# PWR_SW_AND_VI_SENSE.net
KiCad netlist of a schematic drawn in Altium Designer
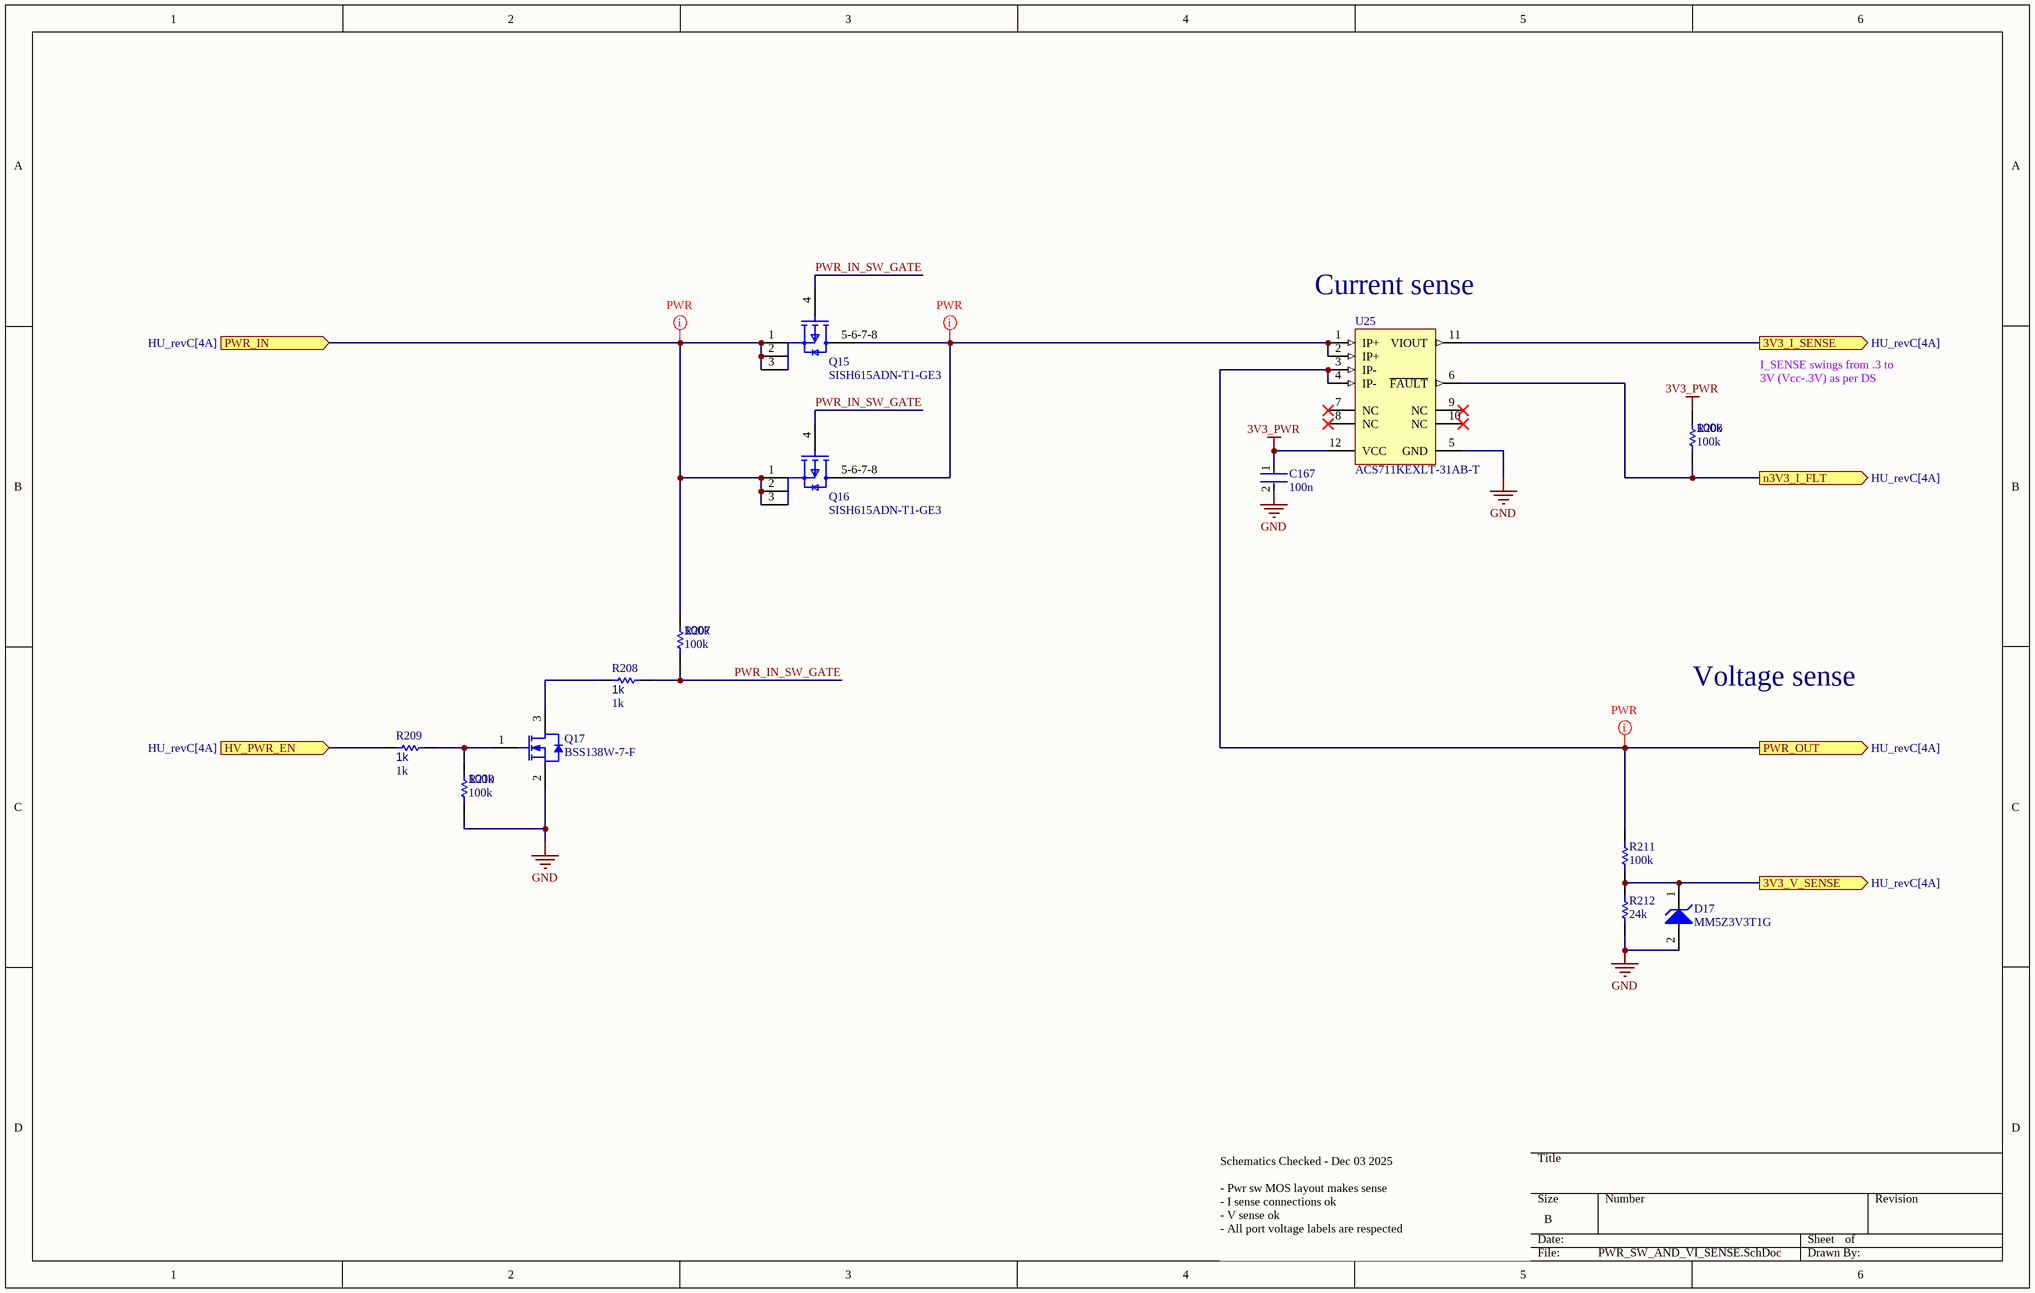
[diagram p0: PWR_SW_AND_VI_SENSE.SchDoc]

(export (version "E")
  (design (tool "Eeschema 10.0.6"))
  (components
    (comp (ref "C167")
      (value "100n")
      (footprint "FP-0402-L_1_0_0_05-W_0_5-IPC_A")
      (description "LARGE PADS, 0402 CAP, CHANGE COMMENT TO MATCH REAL P/N")
      (libsource (lib "Space Concordia") (part "b4654b650e69147ec39a6b967a45e02"))
    )
    (comp (ref "D17")
      (value "MM5Z3V3T1G")
      (footprint "ONSC-SOD-523-2-502-01_V")
      (description "Zener Voltage Regulator, 500 mW, 2-Pin SOD-523, Pb-Free, Tape and Reel")
      (fields (field (name "MANUFACTURER") "On Semiconductor"))
      (libsource (lib "Altium Content Vault") (part "ONSC-K1A2-2"))
    )
    (comp (ref "Q15")
      (value "SISH615ADN-T1-GE3")
      (footprint "SISH615ADN-T1-GE3-Footprint-1")
      (description "Trans MOSFET P-CH 20V 22.1A 8-Pin PowerPAK 1212 EP T/R")
      (libsource (lib "Space Concordia") (part "CMP-013-00036-4"))
    )
    (comp (ref "Q16")
      (value "SISH615ADN-T1-GE3")
      (footprint "SISH615ADN-T1-GE3-Footprint-1")
      (description "Trans MOSFET P-CH 20V 22.1A 8-Pin PowerPAK 1212 EP T/R")
      (libsource (lib "Space Concordia") (part "CMP-013-00036-4"))
    )
    (comp (ref "Q17")
      (value "BSS138W-7-F")
      (footprint "DIOD-SOT323-3_V")
      (fields (field (name "MANUFACTURER") "DiodesIncorporated"))
      (libsource (lib "Altium Content Vault") (part "NEMOS-GSD-3"))
    )
    (comp (ref "R206")
      (value "100k")
      (footprint "R0603B")
      (description "Resistor")
      (fields (field (name "ALTIUM_VALUE") "100k"))
      (libsource (lib "Space Concordia") (part "Resistor"))
    )
    (comp (ref "R207")
      (value "100k")
      (footprint "R0603B")
      (description "Resistor")
      (fields (field (name "ALTIUM_VALUE") "100k"))
      (libsource (lib "Space Concordia") (part "Resistor"))
    )
    (comp (ref "R208")
      (value "1k")
      (footprint "R0603B")
      (description "Resistor")
      (fields (field (name "ALTIUM_VALUE") "1k"))
      (libsource (lib "Space Concordia") (part "Resistor"))
    )
    (comp (ref "R209")
      (value "1k")
      (footprint "R0603B")
      (description "Resistor")
      (fields (field (name "ALTIUM_VALUE") "1k"))
      (libsource (lib "Space Concordia") (part "Resistor"))
    )
    (comp (ref "R210")
      (value "100k")
      (footprint "R0603B")
      (description "Resistor")
      (fields (field (name "ALTIUM_VALUE") "100k"))
      (libsource (lib "Space Concordia") (part "Resistor"))
    )
    (comp (ref "R211")
      (value "100k")
      (footprint "R0603B")
      (description "Resistor")
      (libsource (lib "Space Concordia") (part "Resistor"))
    )
    (comp (ref "R212")
      (value "24k")
      (footprint "R0603B")
      (description "Resistor")
      (libsource (lib "Space Concordia") (part "Resistor"))
    )
    (comp (ref "U25")
      (value "ACS711KEXLT-31AB-T")
      (footprint "ALEG-EX-12_V")
      (libsource (lib "Altium Content Vault") (part "ALEG-ACS711-QFN-12"))
    )
  )
  (nets
    (net (code "1") (name "/3V3_I_SENSE") (class "Default")
      (node (ref "U25") (pin "11") (pinfunction "VIOUT_11") (pintype "output"))
    )
    (net (code "2") (name "/3V3_V_SENSE") (class "Default")
      (node (ref "D17") (pin "1") (pinfunction "K_1") (pintype "passive"))
      (node (ref "R211") (pin "1") (pinfunction "1_1") (pintype "passive"))
      (node (ref "R212") (pin "2") (pinfunction "2_2") (pintype "passive"))
    )
    (net (code "3") (name "/HV_PWR_EN") (class "Default")
      (node (ref "R209") (pin "1") (pinfunction "1_1") (pintype "passive"))
    )
    (net (code "4") (name "/PWR_IN") (class "Default")
      (node (ref "Q15") (pin "1") (pinfunction "S_1") (pintype "passive"))
      (node (ref "Q15") (pin "2") (pinfunction "S_2") (pintype "passive"))
      (node (ref "Q15") (pin "3") (pinfunction "S_3") (pintype "passive"))
      (node (ref "Q16") (pin "1") (pinfunction "S_1") (pintype "passive"))
      (node (ref "Q16") (pin "2") (pinfunction "S_2") (pintype "passive"))
      (node (ref "Q16") (pin "3") (pinfunction "S_3") (pintype "passive"))
      (node (ref "R207") (pin "2") (pinfunction "2_2") (pintype "passive"))
    )
    (net (code "5") (name "/PWR_IN_SW_GATE") (class "Default")
      (node (ref "Q15") (pin "4") (pinfunction "G_4") (pintype "passive"))
      (node (ref "Q16") (pin "4") (pinfunction "G_4") (pintype "passive"))
      (node (ref "R207") (pin "1") (pinfunction "1_1") (pintype "passive"))
      (node (ref "R208") (pin "2") (pinfunction "2_2") (pintype "passive"))
    )
    (net (code "6") (name "/PWR_OUT") (class "Default")
      (node (ref "R211") (pin "2") (pinfunction "2_2") (pintype "passive"))
      (node (ref "U25") (pin "3") (pinfunction "IP-_3") (pintype "input"))
      (node (ref "U25") (pin "4") (pinfunction "IP-_4") (pintype "input"))
    )
    (net (code "7") (name "/n3V3_I_FLT") (class "Default")
      (node (ref "R206") (pin "1") (pinfunction "1_1") (pintype "passive"))
      (node (ref "U25") (pin "6") (pinfunction "~{FAULT}_6") (pintype "output"))
    )
    (net (code "8") (name "3V3_PWR") (class "Default")
      (node (ref "C167") (pin "1") (pinfunction "1_1") (pintype "passive"))
      (node (ref "R206") (pin "2") (pinfunction "2_2") (pintype "passive"))
      (node (ref "U25") (pin "12") (pinfunction "VCC_12") (pintype "power_in"))
    )
    (net (code "9") (name "GND") (class "Default")
      (node (ref "C167") (pin "2") (pinfunction "2_2") (pintype "passive"))
      (node (ref "D17") (pin "2") (pinfunction "A_2") (pintype "passive"))
      (node (ref "Q17") (pin "2") (pinfunction "S_2") (pintype "passive"))
      (node (ref "R210") (pin "1") (pinfunction "1_1") (pintype "passive"))
      (node (ref "R212") (pin "1") (pinfunction "1_1") (pintype "passive"))
      (node (ref "U25") (pin "5") (pinfunction "GND_5") (pintype "power_in"))
    )
    (net (code "10") (name "Net-(Q15-D)") (class "Default")
      (node (ref "Q15") (pin "5-6-7-8") (pinfunction "D_5-6-7-8") (pintype "passive"))
      (node (ref "Q16") (pin "5-6-7-8") (pinfunction "D_5-6-7-8") (pintype "passive"))
      (node (ref "U25") (pin "1") (pinfunction "IP+_1") (pintype "input"))
      (node (ref "U25") (pin "2") (pinfunction "IP+_2") (pintype "input"))
    )
    (net (code "11") (name "Net-(Q17-D)") (class "Default")
      (node (ref "Q17") (pin "3") (pinfunction "D_3") (pintype "passive"))
      (node (ref "R208") (pin "1") (pinfunction "1_1") (pintype "passive"))
    )
    (net (code "12") (name "Net-(Q17-G)") (class "Default")
      (node (ref "Q17") (pin "1") (pinfunction "G_1") (pintype "passive"))
      (node (ref "R209") (pin "2") (pinfunction "2_2") (pintype "passive"))
      (node (ref "R210") (pin "2") (pinfunction "2_2") (pintype "passive"))
    )
    (net (code "13") (name "unconnected-(U25-NC-Pad7)") (class "Default")
      (node (ref "U25") (pin "7") (pinfunction "NC_7") (pintype "passive+no_connect"))
    )
    (net (code "14") (name "unconnected-(U25-NC-Pad8)") (class "Default")
      (node (ref "U25") (pin "8") (pinfunction "NC_8") (pintype "passive+no_connect"))
    )
    (net (code "15") (name "unconnected-(U25-NC-Pad9)") (class "Default")
      (node (ref "U25") (pin "9") (pinfunction "NC_9") (pintype "passive+no_connect"))
    )
    (net (code "16") (name "unconnected-(U25-NC-Pad10)") (class "Default")
      (node (ref "U25") (pin "10") (pinfunction "NC_10") (pintype "passive+no_connect"))
    )
  )
)
